# LoRa_Module.net
KiCad netlist of a schematic drawn in Altium Designer
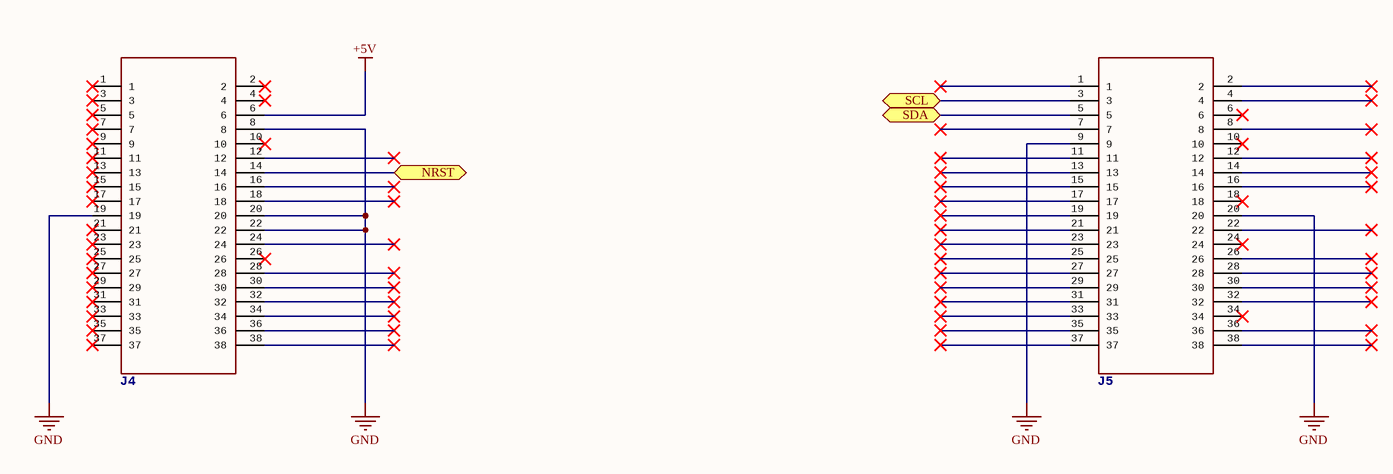
[diagram p0: LoRa_Module.SchDoc]

(export (version "E")
  (design (tool "Eeschema 10.0.6"))
  (components
    (comp (ref "J4")
      (value "SSW-119-01-F-D")
      (footprint "SSW-119-01-F-D")
      (description "CONN RCPT 38POS 0.1 GOLD PCB")
      (fields (field (name "PARTNUMBER") "1095-0013") (field (name "MANUFACTURER") "Samtec Inc."))
      (libsource (lib "RELECTRIFY-PARTSlib_A") (part "SSW-119-01-F-D"))
    )
    (comp (ref "J5")
      (value "SSW-119-01-F-D")
      (footprint "SSW-119-01-F-D")
      (description "CONN RCPT 38POS 0.1 GOLD PCB")
      (fields (field (name "PARTNUMBER") "1095-0013") (field (name "MANUFACTURER") "Samtec Inc."))
      (libsource (lib "RELECTRIFY-PARTSlib_A") (part "SSW-119-01-F-D"))
    )
  )
  (nets
    (net (code "1") (name "+5V") (class "Default")
      (node (ref "J4") (pin "6") (pinfunction "6_6") (pintype "passive"))
    )
    (net (code "2") (name "/NRST") (class "Default")
      (node (ref "J4") (pin "14") (pinfunction "14_14") (pintype "passive"))
    )
    (net (code "3") (name "/SCL") (class "Default")
      (node (ref "J5") (pin "3") (pinfunction "3_3") (pintype "passive"))
    )
    (net (code "4") (name "/SDA") (class "Default")
      (node (ref "J5") (pin "5") (pinfunction "5_5") (pintype "passive"))
    )
    (net (code "5") (name "GND") (class "Default")
      (node (ref "J4") (pin "19") (pinfunction "19_19") (pintype "passive"))
      (node (ref "J4") (pin "20") (pinfunction "20_20") (pintype "passive"))
      (node (ref "J4") (pin "22") (pinfunction "22_22") (pintype "passive"))
      (node (ref "J4") (pin "8") (pinfunction "8_8") (pintype "passive"))
      (node (ref "J5") (pin "20") (pinfunction "20_20") (pintype "passive"))
      (node (ref "J5") (pin "9") (pinfunction "9_9") (pintype "passive"))
    )
    (net (code "6") (name "unconnected-(J4-Pad1)") (class "Default")
      (node (ref "J4") (pin "1") (pinfunction "1_1") (pintype "passive+no_connect"))
    )
    (net (code "7") (name "unconnected-(J4-Pad2)") (class "Default")
      (node (ref "J4") (pin "2") (pinfunction "2_2") (pintype "passive+no_connect"))
    )
    (net (code "8") (name "unconnected-(J4-Pad3)") (class "Default")
      (node (ref "J4") (pin "3") (pinfunction "3_3") (pintype "passive+no_connect"))
    )
    (net (code "9") (name "unconnected-(J4-Pad4)") (class "Default")
      (node (ref "J4") (pin "4") (pinfunction "4_4") (pintype "passive+no_connect"))
    )
    (net (code "10") (name "unconnected-(J4-Pad5)") (class "Default")
      (node (ref "J4") (pin "5") (pinfunction "5_5") (pintype "passive+no_connect"))
    )
    (net (code "11") (name "unconnected-(J4-Pad7)") (class "Default")
      (node (ref "J4") (pin "7") (pinfunction "7_7") (pintype "passive+no_connect"))
    )
    (net (code "12") (name "unconnected-(J4-Pad9)") (class "Default")
      (node (ref "J4") (pin "9") (pinfunction "9_9") (pintype "passive+no_connect"))
    )
    (net (code "13") (name "unconnected-(J4-Pad10)") (class "Default")
      (node (ref "J4") (pin "10") (pinfunction "10_10") (pintype "passive+no_connect"))
    )
    (net (code "14") (name "unconnected-(J4-Pad11)") (class "Default")
      (node (ref "J4") (pin "11") (pinfunction "11_11") (pintype "passive+no_connect"))
    )
    (net (code "15") (name "unconnected-(J4-Pad12)") (class "Default")
      (node (ref "J4") (pin "12") (pinfunction "12_12") (pintype "passive+no_connect"))
    )
    (net (code "16") (name "unconnected-(J4-Pad13)") (class "Default")
      (node (ref "J4") (pin "13") (pinfunction "13_13") (pintype "passive+no_connect"))
    )
    (net (code "17") (name "unconnected-(J4-Pad15)") (class "Default")
      (node (ref "J4") (pin "15") (pinfunction "15_15") (pintype "passive+no_connect"))
    )
    (net (code "18") (name "unconnected-(J4-Pad16)") (class "Default")
      (node (ref "J4") (pin "16") (pinfunction "16_16") (pintype "passive+no_connect"))
    )
    (net (code "19") (name "unconnected-(J4-Pad17)") (class "Default")
      (node (ref "J4") (pin "17") (pinfunction "17_17") (pintype "passive+no_connect"))
    )
    (net (code "20") (name "unconnected-(J4-Pad18)") (class "Default")
      (node (ref "J4") (pin "18") (pinfunction "18_18") (pintype "passive+no_connect"))
    )
    (net (code "21") (name "unconnected-(J4-Pad21)") (class "Default")
      (node (ref "J4") (pin "21") (pinfunction "21_21") (pintype "passive+no_connect"))
    )
    (net (code "22") (name "unconnected-(J4-Pad23)") (class "Default")
      (node (ref "J4") (pin "23") (pinfunction "23_23") (pintype "passive+no_connect"))
    )
    (net (code "23") (name "unconnected-(J4-Pad24)") (class "Default")
      (node (ref "J4") (pin "24") (pinfunction "24_24") (pintype "passive+no_connect"))
    )
    (net (code "24") (name "unconnected-(J4-Pad25)") (class "Default")
      (node (ref "J4") (pin "25") (pinfunction "25_25") (pintype "passive+no_connect"))
    )
    (net (code "25") (name "unconnected-(J4-Pad26)") (class "Default")
      (node (ref "J4") (pin "26") (pinfunction "26_26") (pintype "passive+no_connect"))
    )
    (net (code "26") (name "unconnected-(J4-Pad27)") (class "Default")
      (node (ref "J4") (pin "27") (pinfunction "27_27") (pintype "passive+no_connect"))
    )
    (net (code "27") (name "unconnected-(J4-Pad28)") (class "Default")
      (node (ref "J4") (pin "28") (pinfunction "28_28") (pintype "passive+no_connect"))
    )
    (net (code "28") (name "unconnected-(J4-Pad29)") (class "Default")
      (node (ref "J4") (pin "29") (pinfunction "29_29") (pintype "passive+no_connect"))
    )
    (net (code "29") (name "unconnected-(J4-Pad30)") (class "Default")
      (node (ref "J4") (pin "30") (pinfunction "30_30") (pintype "passive+no_connect"))
    )
    (net (code "30") (name "unconnected-(J4-Pad31)") (class "Default")
      (node (ref "J4") (pin "31") (pinfunction "31_31") (pintype "passive+no_connect"))
    )
    (net (code "31") (name "unconnected-(J4-Pad32)") (class "Default")
      (node (ref "J4") (pin "32") (pinfunction "32_32") (pintype "passive+no_connect"))
    )
    (net (code "32") (name "unconnected-(J4-Pad33)") (class "Default")
      (node (ref "J4") (pin "33") (pinfunction "33_33") (pintype "passive+no_connect"))
    )
    (net (code "33") (name "unconnected-(J4-Pad34)") (class "Default")
      (node (ref "J4") (pin "34") (pinfunction "34_34") (pintype "passive+no_connect"))
    )
    (net (code "34") (name "unconnected-(J4-Pad35)") (class "Default")
      (node (ref "J4") (pin "35") (pinfunction "35_35") (pintype "passive+no_connect"))
    )
    (net (code "35") (name "unconnected-(J4-Pad36)") (class "Default")
      (node (ref "J4") (pin "36") (pinfunction "36_36") (pintype "passive+no_connect"))
    )
    (net (code "36") (name "unconnected-(J4-Pad37)") (class "Default")
      (node (ref "J4") (pin "37") (pinfunction "37_37") (pintype "passive+no_connect"))
    )
    (net (code "37") (name "unconnected-(J4-Pad38)") (class "Default")
      (node (ref "J4") (pin "38") (pinfunction "38_38") (pintype "passive+no_connect"))
    )
    (net (code "38") (name "unconnected-(J5-Pad1)") (class "Default")
      (node (ref "J5") (pin "1") (pinfunction "1_1") (pintype "passive+no_connect"))
    )
    (net (code "39") (name "unconnected-(J5-Pad2)") (class "Default")
      (node (ref "J5") (pin "2") (pinfunction "2_2") (pintype "passive+no_connect"))
    )
    (net (code "40") (name "unconnected-(J5-Pad4)") (class "Default")
      (node (ref "J5") (pin "4") (pinfunction "4_4") (pintype "passive+no_connect"))
    )
    (net (code "41") (name "unconnected-(J5-Pad6)") (class "Default")
      (node (ref "J5") (pin "6") (pinfunction "6_6") (pintype "passive+no_connect"))
    )
    (net (code "42") (name "unconnected-(J5-Pad7)") (class "Default")
      (node (ref "J5") (pin "7") (pinfunction "7_7") (pintype "passive+no_connect"))
    )
    (net (code "43") (name "unconnected-(J5-Pad8)") (class "Default")
      (node (ref "J5") (pin "8") (pinfunction "8_8") (pintype "passive+no_connect"))
    )
    (net (code "44") (name "unconnected-(J5-Pad10)") (class "Default")
      (node (ref "J5") (pin "10") (pinfunction "10_10") (pintype "passive+no_connect"))
    )
    (net (code "45") (name "unconnected-(J5-Pad11)") (class "Default")
      (node (ref "J5") (pin "11") (pinfunction "11_11") (pintype "passive+no_connect"))
    )
    (net (code "46") (name "unconnected-(J5-Pad12)") (class "Default")
      (node (ref "J5") (pin "12") (pinfunction "12_12") (pintype "passive+no_connect"))
    )
    (net (code "47") (name "unconnected-(J5-Pad13)") (class "Default")
      (node (ref "J5") (pin "13") (pinfunction "13_13") (pintype "passive+no_connect"))
    )
    (net (code "48") (name "unconnected-(J5-Pad14)") (class "Default")
      (node (ref "J5") (pin "14") (pinfunction "14_14") (pintype "passive+no_connect"))
    )
    (net (code "49") (name "unconnected-(J5-Pad15)") (class "Default")
      (node (ref "J5") (pin "15") (pinfunction "15_15") (pintype "passive+no_connect"))
    )
    (net (code "50") (name "unconnected-(J5-Pad16)") (class "Default")
      (node (ref "J5") (pin "16") (pinfunction "16_16") (pintype "passive+no_connect"))
    )
    (net (code "51") (name "unconnected-(J5-Pad17)") (class "Default")
      (node (ref "J5") (pin "17") (pinfunction "17_17") (pintype "passive+no_connect"))
    )
    (net (code "52") (name "unconnected-(J5-Pad18)") (class "Default")
      (node (ref "J5") (pin "18") (pinfunction "18_18") (pintype "passive+no_connect"))
    )
    (net (code "53") (name "unconnected-(J5-Pad19)") (class "Default")
      (node (ref "J5") (pin "19") (pinfunction "19_19") (pintype "passive+no_connect"))
    )
    (net (code "54") (name "unconnected-(J5-Pad21)") (class "Default")
      (node (ref "J5") (pin "21") (pinfunction "21_21") (pintype "passive+no_connect"))
    )
    (net (code "55") (name "unconnected-(J5-Pad22)") (class "Default")
      (node (ref "J5") (pin "22") (pinfunction "22_22") (pintype "passive+no_connect"))
    )
    (net (code "56") (name "unconnected-(J5-Pad23)") (class "Default")
      (node (ref "J5") (pin "23") (pinfunction "23_23") (pintype "passive+no_connect"))
    )
    (net (code "57") (name "unconnected-(J5-Pad24)") (class "Default")
      (node (ref "J5") (pin "24") (pinfunction "24_24") (pintype "passive+no_connect"))
    )
    (net (code "58") (name "unconnected-(J5-Pad25)") (class "Default")
      (node (ref "J5") (pin "25") (pinfunction "25_25") (pintype "passive+no_connect"))
    )
    (net (code "59") (name "unconnected-(J5-Pad26)") (class "Default")
      (node (ref "J5") (pin "26") (pinfunction "26_26") (pintype "passive+no_connect"))
    )
    (net (code "60") (name "unconnected-(J5-Pad27)") (class "Default")
      (node (ref "J5") (pin "27") (pinfunction "27_27") (pintype "passive+no_connect"))
    )
    (net (code "61") (name "unconnected-(J5-Pad28)") (class "Default")
      (node (ref "J5") (pin "28") (pinfunction "28_28") (pintype "passive+no_connect"))
    )
    (net (code "62") (name "unconnected-(J5-Pad29)") (class "Default")
      (node (ref "J5") (pin "29") (pinfunction "29_29") (pintype "passive+no_connect"))
    )
    (net (code "63") (name "unconnected-(J5-Pad30)") (class "Default")
      (node (ref "J5") (pin "30") (pinfunction "30_30") (pintype "passive+no_connect"))
    )
    (net (code "64") (name "unconnected-(J5-Pad31)") (class "Default")
      (node (ref "J5") (pin "31") (pinfunction "31_31") (pintype "passive+no_connect"))
    )
    (net (code "65") (name "unconnected-(J5-Pad32)") (class "Default")
      (node (ref "J5") (pin "32") (pinfunction "32_32") (pintype "passive+no_connect"))
    )
    (net (code "66") (name "unconnected-(J5-Pad33)") (class "Default")
      (node (ref "J5") (pin "33") (pinfunction "33_33") (pintype "passive+no_connect"))
    )
    (net (code "67") (name "unconnected-(J5-Pad34)") (class "Default")
      (node (ref "J5") (pin "34") (pinfunction "34_34") (pintype "passive+no_connect"))
    )
    (net (code "68") (name "unconnected-(J5-Pad35)") (class "Default")
      (node (ref "J5") (pin "35") (pinfunction "35_35") (pintype "passive+no_connect"))
    )
    (net (code "69") (name "unconnected-(J5-Pad36)") (class "Default")
      (node (ref "J5") (pin "36") (pinfunction "36_36") (pintype "passive+no_connect"))
    )
    (net (code "70") (name "unconnected-(J5-Pad37)") (class "Default")
      (node (ref "J5") (pin "37") (pinfunction "37_37") (pintype "passive+no_connect"))
    )
    (net (code "71") (name "unconnected-(J5-Pad38)") (class "Default")
      (node (ref "J5") (pin "38") (pinfunction "38_38") (pintype "passive+no_connect"))
    )
  )
)
